# Touch_Switch.net
KiCad netlist of a schematic drawn in EAGLE
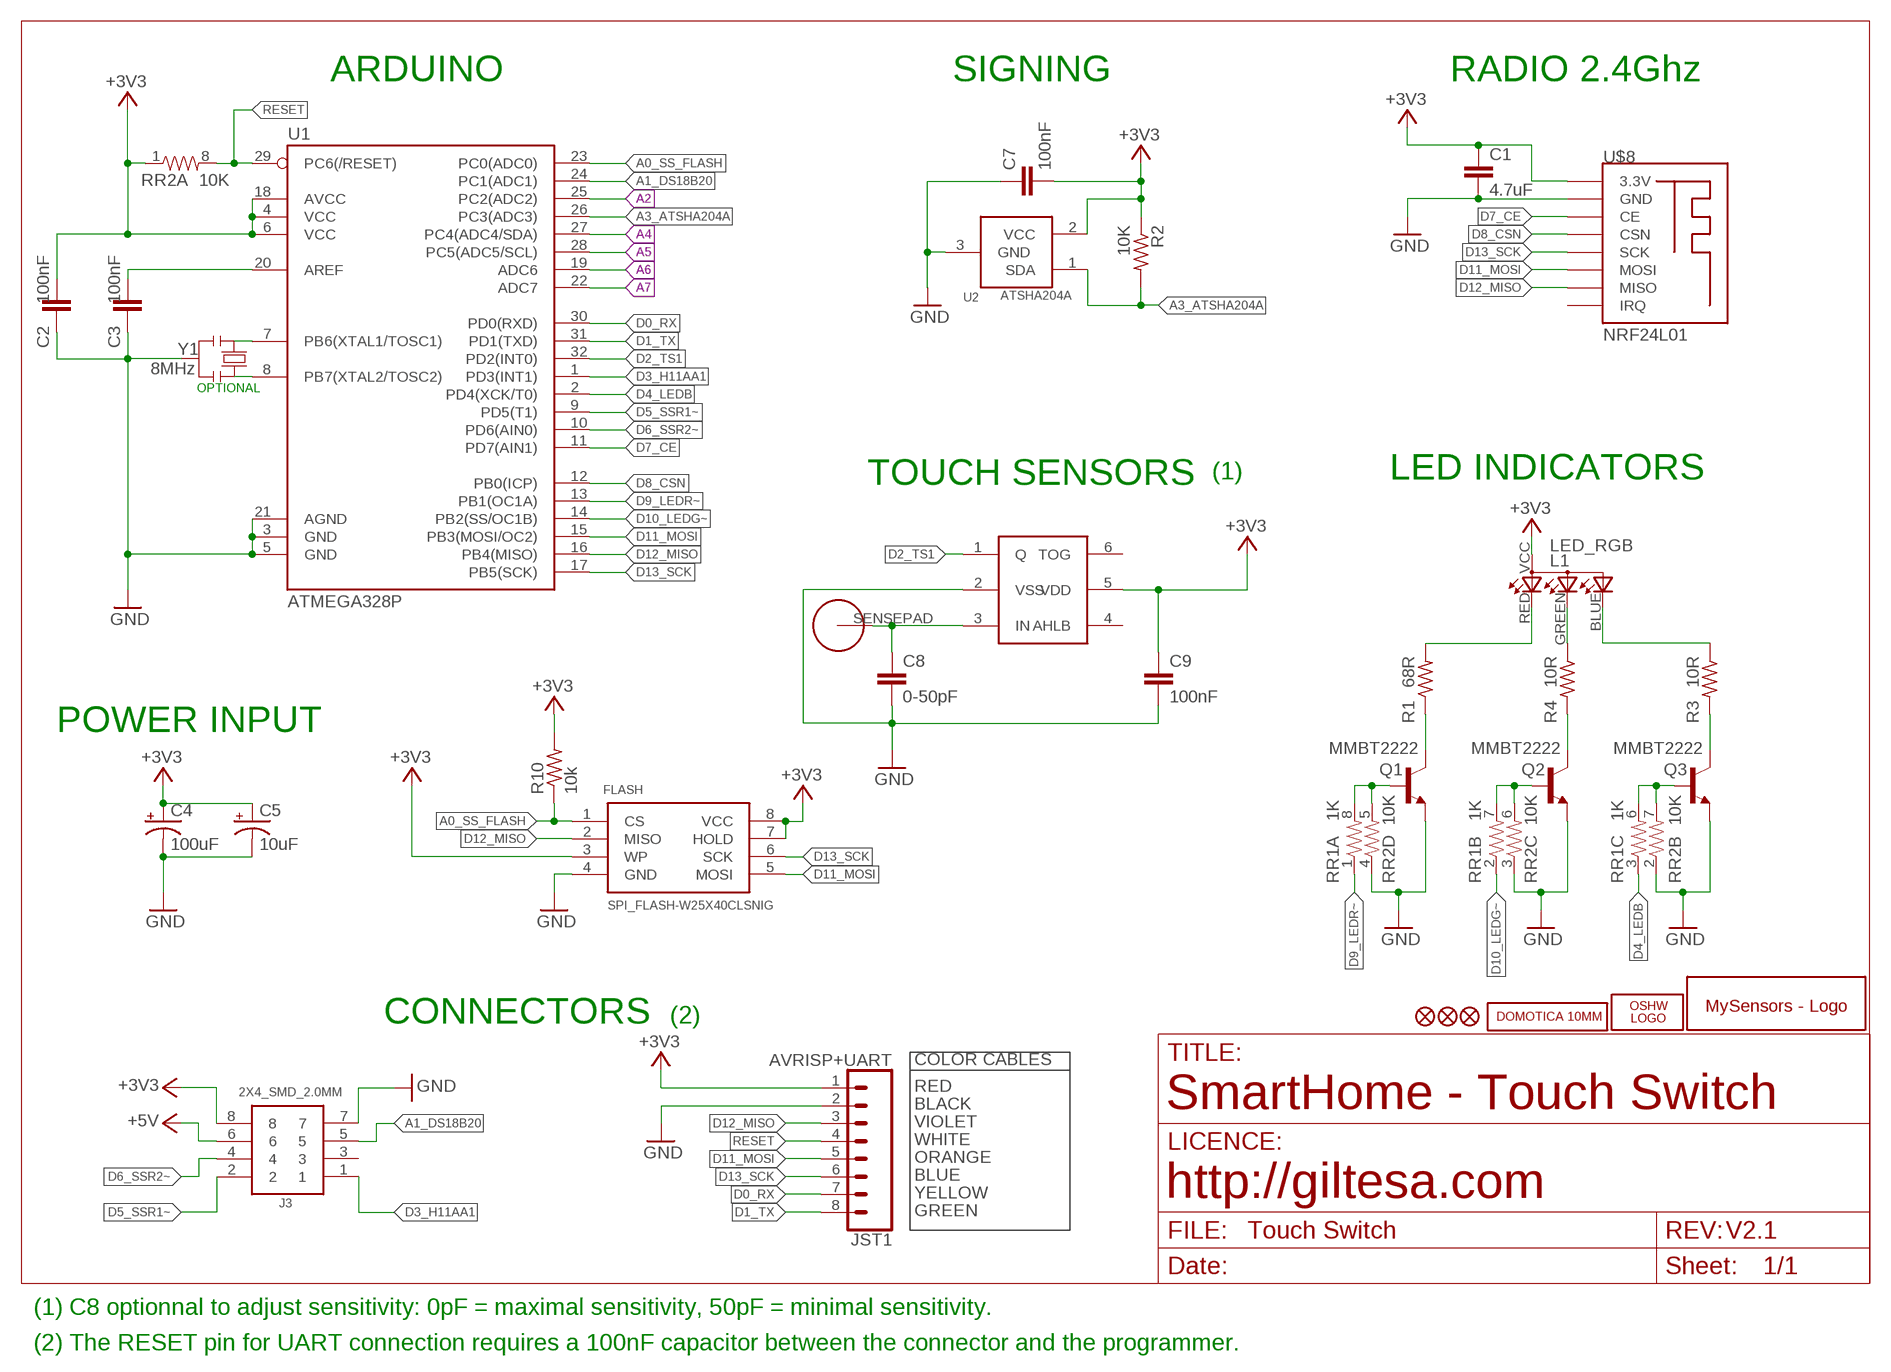
[diagram p0: schematic, sheet 1]

(export (version "E")
  (design (tool "Eeschema 10.0.6"))
  (components
    (comp (ref "C1")
      (value "4.7uF")
      (footprint "eagle-import:C1206")
      (libsource (lib "eagle-import") (part "C1206"))
    )
    (comp (ref "C2")
      (value "100nF")
      (footprint "eagle-import:C0603")
      (libsource (lib "eagle-import") (part "C0603"))
    )
    (comp (ref "C3")
      (value "100nF")
      (footprint "eagle-import:C0603")
      (libsource (lib "eagle-import") (part "C0603"))
    )
    (comp (ref "C4")
      (value "100uF")
      (footprint "eagle-import:EIA3216")
      (libsource (lib "eagle-import") (part "10UF-16V-10%(TANT)"))
    )
    (comp (ref "C5")
      (value "10uF")
      (footprint "eagle-import:EIA3216")
      (libsource (lib "eagle-import") (part "10UF-16V-10%(TANT)"))
    )
    (comp (ref "C7")
      (value "100nF")
      (footprint "eagle-import:C0603")
      (libsource (lib "eagle-import") (part "C0603"))
    )
    (comp (ref "C8")
      (value "0-50pF")
      (footprint "eagle-import:C0603")
      (libsource (lib "eagle-import") (part "C0603"))
    )
    (comp (ref "C9")
      (value "100nF")
      (footprint "eagle-import:C0603")
      (libsource (lib "eagle-import") (part "C0603"))
    )
    (comp (ref "FLASH")
      (value "SPI_FLASH-W25X40CLSNIG")
      (footprint "eagle-import:SO08")
      (libsource (lib "eagle-import") (part "SPI_FLASH-X25XXSMD"))
    )
    (comp (ref "J3")
      (value "2X4_SMD_2.0MM")
      (footprint "eagle-import:2X4_SMD_2.0MM")
      (libsource (lib "eagle-import") (part "2X4_SMD_2.0MM"))
    )
    (comp (ref "JST1")
      (value "AVRISP+UART")
      (footprint "eagle-import:JST-8-1MM-SMD")
      (libsource (lib "eagle-import") (part "JST-8-1MM-SMD"))
    )
    (comp (ref "L1")
      (value "LED_RGB")
      (footprint "eagle-import:LED_RGB_1206_SIDE")
      (libsource (lib "eagle-import") (part "LED_RGB_1206_SIDE"))
    )
    (comp (ref "LOGO1")
      (value "OSHW_LOGO_FILLX0150-NT")
      (footprint "eagle-import:OSHW_FILLX150_NOTEXT")
      (libsource (lib "eagle-import") (part "OSHW_LOGO_FILLX0150-NT"))
    )
    (comp (ref "Q1")
      (value "MMBT2222")
      (footprint "eagle-import:SOT23")
      (libsource (lib "eagle-import") (part "TRANSISTOR_NPNSOT23"))
    )
    (comp (ref "Q2")
      (value "MMBT2222")
      (footprint "eagle-import:SOT23")
      (libsource (lib "eagle-import") (part "TRANSISTOR_NPNSOT23"))
    )
    (comp (ref "Q3")
      (value "MMBT2222")
      (footprint "eagle-import:SOT23")
      (libsource (lib "eagle-import") (part "TRANSISTOR_NPNSOT23"))
    )
    (comp (ref "R1")
      (value "68R")
      (footprint "eagle-import:R0603")
      (libsource (lib "eagle-import") (part "R0603"))
    )
    (comp (ref "R2")
      (value "10K")
      (footprint "eagle-import:R0603")
      (libsource (lib "eagle-import") (part "R0603"))
    )
    (comp (ref "R3")
      (value "10R")
      (footprint "eagle-import:R0603")
      (libsource (lib "eagle-import") (part "R0603"))
    )
    (comp (ref "R4")
      (value "10R")
      (footprint "eagle-import:R0603")
      (libsource (lib "eagle-import") (part "R0603"))
    )
    (comp (ref "R10")
      (value "10k")
      (footprint "eagle-import:R0603")
      (libsource (lib "eagle-import") (part "R0603"))
    )
    (comp (ref "RR1")
      (value "1K")
      (footprint "eagle-import:0603-ARV")
      (libsource (lib "eagle-import") (part "RESISTOR-ARRAY0603-ARV"))
    )
    (comp (ref "RR2")
      (value "10K")
      (footprint "eagle-import:0603-ARV")
      (libsource (lib "eagle-import") (part "RESISTOR-ARRAY0603-ARV"))
    )
    (comp (ref "TTP1")
      (value "TTP223")
      (footprint "eagle-import:SOT-23-6")
      (libsource (lib "eagle-import") (part "TTP223-BA6"))
    )
    (comp (ref "U$1")
      (value "HTTM_SENSEPAD")
      (footprint "eagle-import:HTTM_SENSEPAD")
      (libsource (lib "eagle-import") (part "HTTM_SENSEPAD"))
    )
    (comp (ref "U$2")
      (value "MYSENSORS")
      (footprint "eagle-import:MYSENSORS")
      (libsource (lib "eagle-import") (part "MYSENSORS"))
    )
    (comp (ref "U$5")
      (value "DOMOTICA-10MM")
      (footprint "eagle-import:DOMOTICA-10MM")
      (libsource (lib "eagle-import") (part "DOMOTICA-10MM"))
    )
    (comp (ref "U$6")
      (value "FIDUCIAL1X2")
      (footprint "eagle-import:FIDUCIAL-1X2")
      (libsource (lib "eagle-import") (part "FIDUCIAL1X2"))
    )
    (comp (ref "U$7")
      (value "FIDUCIAL1X2")
      (footprint "eagle-import:FIDUCIAL-1X2")
      (libsource (lib "eagle-import") (part "FIDUCIAL1X2"))
    )
    (comp (ref "U$8")
      (value "NRF24L01")
      (footprint "eagle-import:NRF24L01_SMD")
      (libsource (lib "eagle-import") (part "NRF24L01_SMD"))
    )
    (comp (ref "U$14")
      (value "FIDUCIAL1X2")
      (footprint "eagle-import:FIDUCIAL-1X2")
      (libsource (lib "eagle-import") (part "FIDUCIAL1X2"))
    )
    (comp (ref "U1")
      (value "ATMEGA328P")
      (footprint "eagle-import:TQFP32-08")
      (fields (field (name "PROD_ID") "IC-09069"))
      (libsource (lib "eagle-import") (part "ATMEGA328P_TQFP"))
    )
    (comp (ref "U2")
      (value "ATSHA204A")
      (footprint "eagle-import:SOT23-3")
      (libsource (lib "eagle-import") (part "IC_ATSHA204A_CRYPT"))
    )
    (comp (ref "Y1")
      (value "8MHz")
      (footprint "eagle-import:RESONATOR")
      (libsource (lib "eagle-import") (part "RESONATORMU"))
    )
  )
  (nets
    (net (code "1") (name "+3V3") (class "Default")
      (node (ref "C1") (pin "1") (pinfunction "1_1") (pintype "passive"))
      (node (ref "C2") (pin "2") (pinfunction "2_2") (pintype "passive"))
      (node (ref "C4") (pin "A") (pinfunction "+_A") (pintype "passive"))
      (node (ref "C5") (pin "A") (pinfunction "+_A") (pintype "passive"))
      (node (ref "C7") (pin "2") (pinfunction "2_2") (pintype "passive"))
      (node (ref "C9") (pin "1") (pinfunction "1_1") (pintype "passive"))
      (node (ref "FLASH") (pin "3") (pinfunction "WP_3") (pintype "bidirectional"))
      (node (ref "FLASH") (pin "7") (pinfunction "HOLD_7") (pintype "bidirectional"))
      (node (ref "FLASH") (pin "8") (pinfunction "VCC_8") (pintype "bidirectional"))
      (node (ref "J3") (pin "8") (pinfunction "8_8") (pintype "bidirectional"))
      (node (ref "JST1") (pin "1") (pinfunction "1_1") (pintype "passive"))
      (node (ref "L1") (pin "VCC") (pinfunction "VCC_VCC") (pintype "passive"))
      (node (ref "R10") (pin "2") (pinfunction "2_2") (pintype "passive"))
      (node (ref "R2") (pin "1") (pinfunction "1_1") (pintype "passive"))
      (node (ref "RR2") (pin "1") (pinfunction "1_1") (pintype "passive"))
      (node (ref "TTP1") (pin "5") (pinfunction "VDD_5") (pintype "bidirectional"))
      (node (ref "U$8") (pin "3.3V") (pinfunction "3.3V_3.3V") (pintype "bidirectional"))
      (node (ref "U1") (pin "18") (pinfunction "AVCC_18") (pintype "bidirectional"))
      (node (ref "U1") (pin "4") (pinfunction "VCC_4") (pintype "bidirectional"))
      (node (ref "U1") (pin "6") (pinfunction "VCC_6") (pintype "bidirectional"))
      (node (ref "U2") (pin "2") (pinfunction "VCC_2") (pintype "bidirectional"))
    )
    (net (code "2") (name "+5V") (class "Default")
      (node (ref "J3") (pin "6") (pinfunction "6_6") (pintype "bidirectional"))
    )
    (net (code "3") (name "/D5_SSR1~{}") (class "Default")
      (node (ref "J3") (pin "2") (pinfunction "2_2") (pintype "bidirectional"))
      (node (ref "U1") (pin "9") (pinfunction "PD5(T1)_9") (pintype "bidirectional"))
    )
    (net (code "4") (name "/D6_SSR2~{}") (class "Default")
      (node (ref "J3") (pin "4") (pinfunction "4_4") (pintype "bidirectional"))
      (node (ref "U1") (pin "10") (pinfunction "PD6(AIN0)_10") (pintype "bidirectional"))
    )
    (net (code "5") (name "/D9_LEDR~{}") (class "Default")
      (node (ref "RR1") (pin "1") (pinfunction "1_1") (pintype "passive"))
      (node (ref "U1") (pin "13") (pinfunction "PB1(OC1A)_13") (pintype "bidirectional"))
    )
    (net (code "6") (name "/D10_LEDG~{}") (class "Default")
      (node (ref "RR1") (pin "2") (pinfunction "1_2") (pintype "passive"))
      (node (ref "U1") (pin "14") (pinfunction "PB2(SS/OC1B)_14") (pintype "bidirectional"))
    )
    (net (code "7") (name "A0_SS_FLASH") (class "Default")
      (node (ref "FLASH") (pin "1") (pinfunction "CS_1") (pintype "bidirectional"))
      (node (ref "R10") (pin "1") (pinfunction "1_1") (pintype "passive"))
      (node (ref "U1") (pin "23") (pinfunction "PC0(ADC0)_23") (pintype "bidirectional"))
    )
    (net (code "8") (name "A1_DS18B20") (class "Default")
      (node (ref "J3") (pin "5") (pinfunction "5_5") (pintype "bidirectional"))
      (node (ref "U1") (pin "24") (pinfunction "PC1(ADC1)_24") (pintype "bidirectional"))
    )
    (net (code "9") (name "A2") (class "Default")
      (node (ref "U1") (pin "25") (pinfunction "PC2(ADC2)_25") (pintype "bidirectional"))
    )
    (net (code "10") (name "A3_ATSHA204A") (class "Default")
      (node (ref "R2") (pin "2") (pinfunction "2_2") (pintype "passive"))
      (node (ref "U1") (pin "26") (pinfunction "PC3(ADC3)_26") (pintype "bidirectional"))
      (node (ref "U2") (pin "1") (pinfunction "SDA_1") (pintype "bidirectional"))
    )
    (net (code "11") (name "A4") (class "Default")
      (node (ref "U1") (pin "27") (pinfunction "PC4(ADC4/SDA)_27") (pintype "bidirectional"))
    )
    (net (code "12") (name "A5") (class "Default")
      (node (ref "U1") (pin "28") (pinfunction "PC5(ADC5/SCL)_28") (pintype "bidirectional"))
    )
    (net (code "13") (name "A6") (class "Default")
      (node (ref "U1") (pin "19") (pinfunction "ADC6_19") (pintype "bidirectional"))
    )
    (net (code "14") (name "A7") (class "Default")
      (node (ref "U1") (pin "22") (pinfunction "ADC7_22") (pintype "bidirectional"))
    )
    (net (code "15") (name "D0_RX") (class "Default")
      (node (ref "JST1") (pin "7") (pinfunction "7_7") (pintype "passive"))
      (node (ref "U1") (pin "30") (pinfunction "PD0(RXD)_30") (pintype "bidirectional"))
    )
    (net (code "16") (name "D1_TX") (class "Default")
      (node (ref "JST1") (pin "8") (pinfunction "8_8") (pintype "passive"))
      (node (ref "U1") (pin "31") (pinfunction "PD1(TXD)_31") (pintype "bidirectional"))
    )
    (net (code "17") (name "D2_TS1") (class "Default")
      (node (ref "TTP1") (pin "1") (pinfunction "Q_1") (pintype "bidirectional"))
      (node (ref "U1") (pin "32") (pinfunction "PD2(INT0)_32") (pintype "bidirectional"))
    )
    (net (code "18") (name "D3_H11AA1") (class "Default")
      (node (ref "J3") (pin "1") (pinfunction "1_1") (pintype "bidirectional"))
      (node (ref "U1") (pin "1") (pinfunction "PD3(INT1)_1") (pintype "bidirectional"))
    )
    (net (code "19") (name "D4_LEDB") (class "Default")
      (node (ref "RR1") (pin "3") (pinfunction "1_3") (pintype "passive"))
      (node (ref "U1") (pin "2") (pinfunction "PD4(XCK/T0)_2") (pintype "bidirectional"))
    )
    (net (code "20") (name "D7_CE") (class "Default")
      (node (ref "U$8") (pin "CE") (pinfunction "CE_CE") (pintype "bidirectional"))
      (node (ref "U1") (pin "11") (pinfunction "PD7(AIN1)_11") (pintype "bidirectional"))
    )
    (net (code "21") (name "D8_CSN") (class "Default")
      (node (ref "U$8") (pin "CSN") (pinfunction "CSN_CSN") (pintype "bidirectional"))
      (node (ref "U1") (pin "12") (pinfunction "PB0(ICP)_12") (pintype "bidirectional"))
    )
    (net (code "22") (name "D11_MOSI") (class "Default")
      (node (ref "FLASH") (pin "5") (pinfunction "MOSI_5") (pintype "bidirectional"))
      (node (ref "JST1") (pin "5") (pinfunction "5_5") (pintype "passive"))
      (node (ref "U$8") (pin "MOSI") (pinfunction "MOSI_MOSI") (pintype "bidirectional"))
      (node (ref "U1") (pin "15") (pinfunction "PB3(MOSI/OC2)_15") (pintype "bidirectional"))
    )
    (net (code "23") (name "D12_MISO") (class "Default")
      (node (ref "FLASH") (pin "2") (pinfunction "MISO_2") (pintype "bidirectional"))
      (node (ref "JST1") (pin "3") (pinfunction "3_3") (pintype "passive"))
      (node (ref "U$8") (pin "MISO") (pinfunction "MISO_MISO") (pintype "bidirectional"))
      (node (ref "U1") (pin "16") (pinfunction "PB4(MISO)_16") (pintype "bidirectional"))
    )
    (net (code "24") (name "D13_SCK") (class "Default")
      (node (ref "FLASH") (pin "6") (pinfunction "SCK_6") (pintype "bidirectional"))
      (node (ref "JST1") (pin "6") (pinfunction "6_6") (pintype "passive"))
      (node (ref "U$8") (pin "SCK") (pinfunction "SCK_SCK") (pintype "bidirectional"))
      (node (ref "U1") (pin "17") (pinfunction "PB5(SCK)_17") (pintype "bidirectional"))
    )
    (net (code "25") (name "GND") (class "Default")
      (node (ref "C1") (pin "2") (pinfunction "2_2") (pintype "passive"))
      (node (ref "C2") (pin "1") (pinfunction "1_1") (pintype "passive"))
      (node (ref "C3") (pin "1") (pinfunction "1_1") (pintype "passive"))
      (node (ref "C4") (pin "C") (pinfunction "-_C") (pintype "passive"))
      (node (ref "C5") (pin "C") (pinfunction "-_C") (pintype "passive"))
      (node (ref "C7") (pin "1") (pinfunction "1_1") (pintype "passive"))
      (node (ref "C8") (pin "2") (pinfunction "2_2") (pintype "passive"))
      (node (ref "C9") (pin "2") (pinfunction "2_2") (pintype "passive"))
      (node (ref "FLASH") (pin "4") (pinfunction "GND_4") (pintype "bidirectional"))
      (node (ref "J3") (pin "7") (pinfunction "7_7") (pintype "bidirectional"))
      (node (ref "JST1") (pin "2") (pinfunction "2_2") (pintype "passive"))
      (node (ref "Q1") (pin "2") (pinfunction "E_2") (pintype "passive"))
      (node (ref "Q2") (pin "2") (pinfunction "E_2") (pintype "passive"))
      (node (ref "Q3") (pin "2") (pinfunction "E_2") (pintype "passive"))
      (node (ref "RR2") (pin "2") (pinfunction "1_2") (pintype "passive"))
      (node (ref "RR2") (pin "3") (pinfunction "1_3") (pintype "passive"))
      (node (ref "RR2") (pin "4") (pinfunction "1_4") (pintype "passive"))
      (node (ref "TTP1") (pin "2") (pinfunction "VSS_2") (pintype "bidirectional"))
      (node (ref "U$8") (pin "GND") (pinfunction "GND_GND") (pintype "bidirectional"))
      (node (ref "U1") (pin "21") (pinfunction "AGND_21") (pintype "bidirectional"))
      (node (ref "U1") (pin "3") (pinfunction "GND_3") (pintype "bidirectional"))
      (node (ref "U1") (pin "5") (pinfunction "GND_5") (pintype "bidirectional"))
      (node (ref "U2") (pin "3") (pinfunction "GND_3") (pintype "bidirectional"))
      (node (ref "Y1") (pin "2") (pinfunction "2_2") (pintype "passive"))
    )
    (net (code "26") (name "Net-(L1-PadBLUE)") (class "Default")
      (node (ref "L1") (pin "BLUE") (pinfunction "BLUE_BLUE") (pintype "passive"))
      (node (ref "R3") (pin "1") (pinfunction "1_1") (pintype "passive"))
    )
    (net (code "27") (name "Net-(L1-PadGREEN)") (class "Default")
      (node (ref "L1") (pin "GREEN") (pinfunction "GREEN_GREEN") (pintype "passive"))
      (node (ref "R4") (pin "1") (pinfunction "1_1") (pintype "passive"))
    )
    (net (code "28") (name "Net-(L1-PadRED)") (class "Default")
      (node (ref "L1") (pin "RED") (pinfunction "RED_RED") (pintype "passive"))
      (node (ref "R1") (pin "2") (pinfunction "2_2") (pintype "passive"))
    )
    (net (code "29") (name "Net-(Q1-B)") (class "Default")
      (node (ref "Q1") (pin "1") (pinfunction "B_1") (pintype "passive"))
      (node (ref "RR1") (pin "8") (pinfunction "2_8") (pintype "passive"))
      (node (ref "RR2") (pin "5") (pinfunction "2_5") (pintype "passive"))
    )
    (net (code "30") (name "Net-(Q1-C)") (class "Default")
      (node (ref "Q1") (pin "3") (pinfunction "C_3") (pintype "passive"))
      (node (ref "R1") (pin "1") (pinfunction "1_1") (pintype "passive"))
    )
    (net (code "31") (name "Net-(Q2-B)") (class "Default")
      (node (ref "Q2") (pin "1") (pinfunction "B_1") (pintype "passive"))
      (node (ref "RR1") (pin "7") (pinfunction "2_7") (pintype "passive"))
      (node (ref "RR2") (pin "6") (pinfunction "2_6") (pintype "passive"))
    )
    (net (code "32") (name "Net-(Q2-C)") (class "Default")
      (node (ref "Q2") (pin "3") (pinfunction "C_3") (pintype "passive"))
      (node (ref "R4") (pin "2") (pinfunction "2_2") (pintype "passive"))
    )
    (net (code "33") (name "Net-(Q3-B)") (class "Default")
      (node (ref "Q3") (pin "1") (pinfunction "B_1") (pintype "passive"))
      (node (ref "RR1") (pin "6") (pinfunction "2_6") (pintype "passive"))
      (node (ref "RR2") (pin "7") (pinfunction "2_7") (pintype "passive"))
    )
    (net (code "34") (name "Net-(Q3-C)") (class "Default")
      (node (ref "Q3") (pin "3") (pinfunction "C_3") (pintype "passive"))
      (node (ref "R3") (pin "2") (pinfunction "2_2") (pintype "passive"))
    )
    (net (code "35") (name "Net-(TTP1-IN)") (class "Default")
      (node (ref "C8") (pin "1") (pinfunction "1_1") (pintype "passive"))
      (node (ref "TTP1") (pin "3") (pinfunction "IN_3") (pintype "bidirectional"))
      (node (ref "U$1") (pin "SENSEPAD") (pinfunction "SENSEPAD_SENSEPAD") (pintype "bidirectional"))
    )
    (net (code "36") (name "Net-(U1-AREF)") (class "Default")
      (node (ref "C3") (pin "2") (pinfunction "2_2") (pintype "passive"))
      (node (ref "U1") (pin "20") (pinfunction "AREF_20") (pintype "bidirectional"))
    )
    (net (code "37") (name "Net-(U1-PB6(XTAL1{slash}TOSC1))") (class "Default")
      (node (ref "U1") (pin "7") (pinfunction "PB6(XTAL1/TOSC1)_7") (pintype "bidirectional"))
      (node (ref "Y1") (pin "1") (pinfunction "1_1") (pintype "passive"))
    )
    (net (code "38") (name "Net-(U1-PB7(XTAL2{slash}TOSC2))") (class "Default")
      (node (ref "U1") (pin "8") (pinfunction "PB7(XTAL2/TOSC2)_8") (pintype "bidirectional"))
      (node (ref "Y1") (pin "3") (pinfunction "3_3") (pintype "passive"))
    )
    (net (code "39") (name "RESET") (class "Default")
      (node (ref "JST1") (pin "4") (pinfunction "4_4") (pintype "passive"))
      (node (ref "RR2") (pin "8") (pinfunction "2_8") (pintype "passive"))
      (node (ref "U1") (pin "29") (pinfunction "PC6(/RESET)_29") (pintype "bidirectional"))
    )
    (net (code "40") (name "unconnected-(J3-Pad3)") (class "Default")
      (node (ref "J3") (pin "3") (pinfunction "3_3") (pintype "bidirectional"))
    )
    (net (code "41") (name "unconnected-(TTP1-AHLB-Pad4)") (class "Default")
      (node (ref "TTP1") (pin "4") (pinfunction "AHLB_4") (pintype "bidirectional"))
    )
    (net (code "42") (name "unconnected-(TTP1-TOG-Pad6)") (class "Default")
      (node (ref "TTP1") (pin "6") (pinfunction "TOG_6") (pintype "bidirectional"))
    )
    (net (code "43") (name "unconnected-(U$8-PadIRQ)") (class "Default")
      (node (ref "U$8") (pin "IRQ") (pinfunction "IRQ_IRQ") (pintype "bidirectional"))
    )
  )
)
